# BEESP_CODE_mpu.net
KiCad netlist of a schematic drawn in Altium Designer
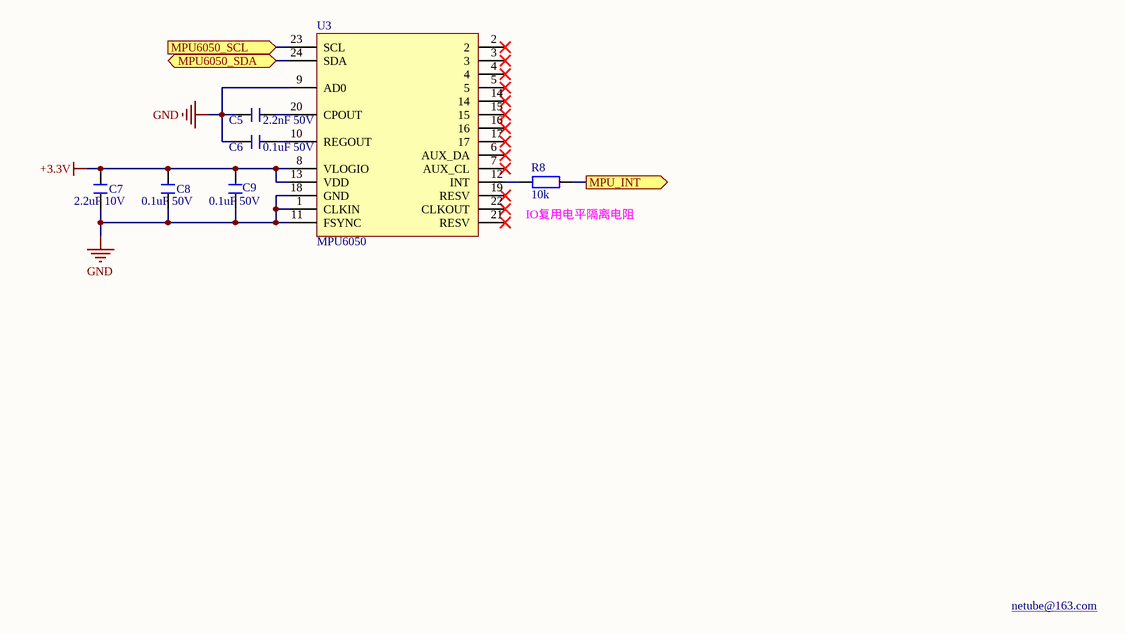
[diagram p0: BEESP_CODE_mpu.SchDoc]

(export (version "E")
  (design (tool "Eeschema 10.0.6"))
  (components
    (comp (ref "C5")
      (value "2.2nF 50V")
      (footprint "C 0402_L")
      (description "贴片电容")
      (libsource (lib "0.1 - 电阻-电容-电感") (part "C"))
    )
    (comp (ref "C6")
      (value "0.1uF 50V")
      (footprint "C 0402_L")
      (description "贴片电容")
      (libsource (lib "0.1 - 电阻-电容-电感") (part "C"))
    )
    (comp (ref "C7")
      (value "2.2uF 10V")
      (footprint "C 0402_L")
      (description "贴片电容")
      (libsource (lib "0.1 - 电阻-电容-电感") (part "C"))
    )
    (comp (ref "C8")
      (value "0.1uF 50V")
      (footprint "C 0402_L")
      (description "贴片电容")
      (libsource (lib "0.1 - 电阻-电容-电感") (part "C"))
    )
    (comp (ref "C9")
      (value "0.1uF 50V")
      (footprint "C 0402_L")
      (description "贴片电容")
      (libsource (lib "0.1 - 电阻-电容-电感") (part "C"))
    )
    (comp (ref "R8")
      (value "10k")
      (footprint "R 0402_L")
      (description "贴片电阻")
      (libsource (lib "0.1 - 电阻-电容-电感") (part "R"))
    )
    (comp (ref "U3")
      (value "MPU6050")
      (footprint "QFN24 4x4_NOPAD")
      (description "三轴加速度+三轴陀螺仪")
      (libsource (lib "1.0 - 常见芯片") (part "MPU6050"))
    )
  )
  (nets
    (net (code "1") (name "+3.3V") (class "Default")
      (node (ref "C7") (pin "1") (pinfunction "1_1") (pintype "passive"))
      (node (ref "C8") (pin "1") (pinfunction "1_1") (pintype "passive"))
      (node (ref "C9") (pin "1") (pinfunction "1_1") (pintype "passive"))
      (node (ref "U3") (pin "13") (pinfunction "VDD_13") (pintype "passive"))
      (node (ref "U3") (pin "8") (pinfunction "VLOGIO_8") (pintype "passive"))
    )
    (net (code "2") (name "/MPU6050_SCL") (class "Default")
      (node (ref "U3") (pin "23") (pinfunction "SCL_23") (pintype "passive"))
    )
    (net (code "3") (name "/MPU6050_SDA") (class "Default")
      (node (ref "U3") (pin "24") (pinfunction "SDA_24") (pintype "passive"))
    )
    (net (code "4") (name "/MPU_INT") (class "Default")
      (node (ref "R8") (pin "1") (pinfunction "1_1") (pintype "passive"))
    )
    (net (code "5") (name "GND") (class "Default")
      (node (ref "C5") (pin "1") (pinfunction "1_1") (pintype "passive"))
      (node (ref "C6") (pin "1") (pinfunction "1_1") (pintype "passive"))
      (node (ref "C7") (pin "2") (pinfunction "2_2") (pintype "passive"))
      (node (ref "C8") (pin "2") (pinfunction "2_2") (pintype "passive"))
      (node (ref "C9") (pin "2") (pinfunction "2_2") (pintype "passive"))
      (node (ref "U3") (pin "1") (pinfunction "CLKIN_1") (pintype "passive"))
      (node (ref "U3") (pin "11") (pinfunction "FSYNC_11") (pintype "passive"))
      (node (ref "U3") (pin "18") (pinfunction "GND_18") (pintype "passive"))
      (node (ref "U3") (pin "9") (pinfunction "AD0_9") (pintype "passive"))
    )
    (net (code "6") (name "Net-(U3-CPOUT)") (class "Default")
      (node (ref "C5") (pin "2") (pinfunction "2_2") (pintype "passive"))
      (node (ref "U3") (pin "20") (pinfunction "CPOUT_20") (pintype "passive"))
    )
    (net (code "7") (name "Net-(U3-INT)") (class "Default")
      (node (ref "R8") (pin "2") (pinfunction "2_2") (pintype "passive"))
      (node (ref "U3") (pin "12") (pinfunction "INT_12") (pintype "passive"))
    )
    (net (code "8") (name "Net-(U3-REGOUT)") (class "Default")
      (node (ref "C6") (pin "2") (pinfunction "2_2") (pintype "passive"))
      (node (ref "U3") (pin "10") (pinfunction "REGOUT_10") (pintype "passive"))
    )
    (net (code "9") (name "unconnected-(U3-AUX_CL-Pad7)") (class "Default")
      (node (ref "U3") (pin "7") (pinfunction "AUX_CL_7") (pintype "passive+no_connect"))
    )
    (net (code "10") (name "unconnected-(U3-AUX_DA-Pad6)") (class "Default")
      (node (ref "U3") (pin "6") (pinfunction "AUX_DA_6") (pintype "passive+no_connect"))
    )
    (net (code "11") (name "unconnected-(U3-CLKOUT-Pad22)") (class "Default")
      (node (ref "U3") (pin "22") (pinfunction "CLKOUT_22") (pintype "passive+no_connect"))
    )
    (net (code "12") (name "unconnected-(U3-Pad2)") (class "Default")
      (node (ref "U3") (pin "2") (pinfunction "2_2") (pintype "passive+no_connect"))
    )
    (net (code "13") (name "unconnected-(U3-Pad3)") (class "Default")
      (node (ref "U3") (pin "3") (pinfunction "3_3") (pintype "passive+no_connect"))
    )
    (net (code "14") (name "unconnected-(U3-Pad4)") (class "Default")
      (node (ref "U3") (pin "4") (pinfunction "4_4") (pintype "passive+no_connect"))
    )
    (net (code "15") (name "unconnected-(U3-Pad5)") (class "Default")
      (node (ref "U3") (pin "5") (pinfunction "5_5") (pintype "passive+no_connect"))
    )
    (net (code "16") (name "unconnected-(U3-Pad14)") (class "Default")
      (node (ref "U3") (pin "14") (pinfunction "14_14") (pintype "passive+no_connect"))
    )
    (net (code "17") (name "unconnected-(U3-Pad15)") (class "Default")
      (node (ref "U3") (pin "15") (pinfunction "15_15") (pintype "passive+no_connect"))
    )
    (net (code "18") (name "unconnected-(U3-Pad16)") (class "Default")
      (node (ref "U3") (pin "16") (pinfunction "16_16") (pintype "passive+no_connect"))
    )
    (net (code "19") (name "unconnected-(U3-Pad17)") (class "Default")
      (node (ref "U3") (pin "17") (pinfunction "17_17") (pintype "passive+no_connect"))
    )
    (net (code "20") (name "unconnected-(U3-RESV-Pad19)") (class "Default")
      (node (ref "U3") (pin "19") (pinfunction "RESV_19") (pintype "passive+no_connect"))
    )
    (net (code "21") (name "unconnected-(U3-RESV-Pad21)") (class "Default")
      (node (ref "U3") (pin "21") (pinfunction "RESV_21") (pintype "passive+no_connect"))
    )
  )
)
